# PinBoardJTAG20_10.net
KiCad netlist of a schematic drawn in Altium Designer
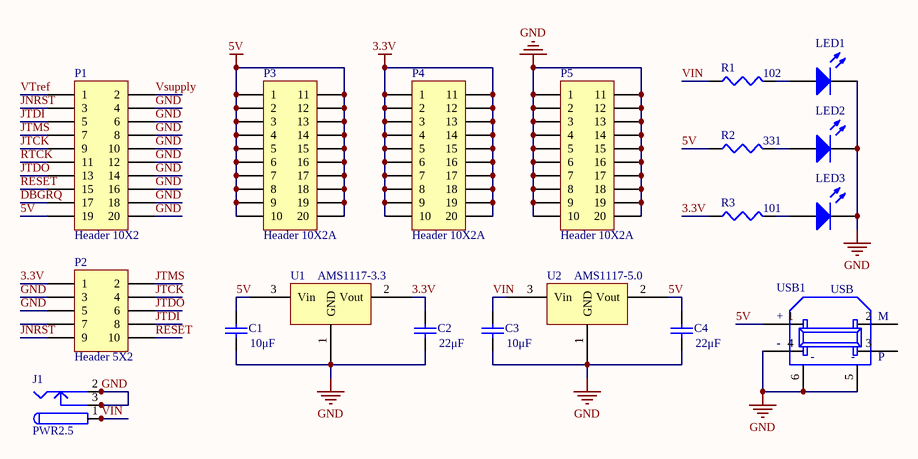
[diagram p0: PinBoardJTAG20_10.SchDoc]

(export (version "E")
  (design (tool "Eeschema 10.0.6"))
  (components
    (comp (ref "C1")
      (value "10μF")
      (footprint "1608[0603]")
      (description "Capacitor (Semiconductor SIM Model)")
      (fields (field (name "Comment") "Cap Semi") (field (name "PUBLISHER") "Altium Limited"))
      (libsource (lib "Miscellaneous Devices") (part "Cap Semi"))
    )
    (comp (ref "C2")
      (value "22μF")
      (footprint "1608[0603]")
      (description "Capacitor (Semiconductor SIM Model)")
      (fields (field (name "Comment") "Cap Semi") (field (name "PUBLISHER") "Altium Limited"))
      (libsource (lib "Miscellaneous Devices") (part "Cap Semi"))
    )
    (comp (ref "C3")
      (value "10μF")
      (footprint "1608[0603]")
      (description "Capacitor (Semiconductor SIM Model)")
      (fields (field (name "Comment") "Cap Semi") (field (name "PUBLISHER") "Altium Limited"))
      (libsource (lib "Miscellaneous Devices") (part "Cap Semi"))
    )
    (comp (ref "C4")
      (value "22μF")
      (footprint "1608[0603]")
      (description "Capacitor (Semiconductor SIM Model)")
      (fields (field (name "Comment") "Cap Semi") (field (name "PUBLISHER") "Altium Limited"))
      (libsource (lib "Miscellaneous Devices") (part "Cap Semi"))
    )
    (comp (ref "J1")
      (value "PWR2.5")
      (footprint "KLD-0202")
      (description "Low Voltage Power Supply Connector")
      (fields (field (name "PUBLISHER") "Altium Limited"))
      (libsource (lib "Miscellaneous Connectors") (part "PWR2.5"))
    )
    (comp (ref "LED1")
      (value "LED1")
      (footprint "BAT-2")
      (description "Typical RED GaAs LED")
      (fields (field (name "PUBLISHER") "Altium Limited"))
      (libsource (lib "Miscellaneous Devices") (part "LED1"))
    )
    (comp (ref "LED2")
      (value "LED1")
      (footprint "BAT-2")
      (description "Typical RED GaAs LED")
      (fields (field (name "PUBLISHER") "Altium Limited"))
      (libsource (lib "Miscellaneous Devices") (part "LED1"))
    )
    (comp (ref "LED3")
      (value "LED1")
      (footprint "BAT-2")
      (description "Typical RED GaAs LED")
      (fields (field (name "PUBLISHER") "Altium Limited"))
      (libsource (lib "Miscellaneous Devices") (part "LED1"))
    )
    (comp (ref "P1")
      (value "Header 10X2")
      (footprint "HDR2X10")
      (description "Header, 10-Pin, Dual row")
      (fields (field (name "PUBLISHER") "Altium Limited"))
      (libsource (lib "Miscellaneous Connectors") (part "Header 10X2"))
    )
    (comp (ref "P2")
      (value "Header 5X2")
      (footprint "HDR2X5")
      (description "Header, 5-Pin, Dual row")
      (fields (field (name "PUBLISHER") "Altium Limited"))
      (libsource (lib "Miscellaneous Connectors") (part "Header 5X2"))
    )
    (comp (ref "P3")
      (value "Header 10X2A")
      (footprint "HDR2X10_CEN")
      (description "Header, 10-Pin, Dual row")
      (fields (field (name "PUBLISHER") "Altium Limited"))
      (libsource (lib "Miscellaneous Connectors") (part "Header 10X2A"))
    )
    (comp (ref "P4")
      (value "Header 10X2A")
      (footprint "HDR2X10_CEN")
      (description "Header, 10-Pin, Dual row")
      (fields (field (name "PUBLISHER") "Altium Limited"))
      (libsource (lib "Miscellaneous Connectors") (part "Header 10X2A"))
    )
    (comp (ref "P5")
      (value "Header 10X2A")
      (footprint "HDR2X10_CEN")
      (description "Header, 10-Pin, Dual row")
      (fields (field (name "PUBLISHER") "Altium Limited"))
      (libsource (lib "Miscellaneous Connectors") (part "Header 10X2A"))
    )
    (comp (ref "R1")
      (value "102")
      (footprint "6-0805_N")
      (description "Resistor")
      (fields (field (name "Comment") "Res3") (field (name "PUBLISHER") "Altium Limited"))
      (libsource (lib "Miscellaneous Devices") (part "Res3"))
    )
    (comp (ref "R2")
      (value "331")
      (footprint "6-0805_N")
      (description "Resistor")
      (fields (field (name "Comment") "Res3") (field (name "PUBLISHER") "Altium Limited"))
      (libsource (lib "Miscellaneous Devices") (part "Res3"))
    )
    (comp (ref "R3")
      (value "101")
      (footprint "6-0805_N")
      (description "Resistor")
      (fields (field (name "Comment") "Res3") (field (name "PUBLISHER") "Altium Limited"))
      (libsource (lib "Miscellaneous Devices") (part "Res3"))
    )
    (comp (ref "U1")
      (value "AMS1117-3.3")
      (footprint "AMS1117-SOT223")
      (libsource (lib "Common") (part "AMS1117-3.3"))
    )
    (comp (ref "U2")
      (value "AMS1117-5.0")
      (footprint "AMS1117-SOT223")
      (libsource (lib "Common") (part "AMS1117-5.0"))
    )
    (comp (ref "USB1") (value "USB") (footprint "MICROUSB_D2S6") (libsource (lib "Common") (part "USB")))
  )
  (nets
    (net (code "1") (name "/DBGRQ") (class "Default")
      (node (ref "P1") (pin "17") (pinfunction "17_17") (pintype "passive"))
    )
    (net (code "2") (name "/JNRST") (class "Default")
      (node (ref "P1") (pin "3") (pinfunction "3_3") (pintype "passive"))
      (node (ref "P2") (pin "9") (pinfunction "9_9") (pintype "passive"))
    )
    (net (code "3") (name "/JTCK") (class "Default")
      (node (ref "P1") (pin "9") (pinfunction "9_9") (pintype "passive"))
      (node (ref "P2") (pin "4") (pinfunction "4_4") (pintype "passive"))
    )
    (net (code "4") (name "/JTDI") (class "Default")
      (node (ref "P1") (pin "5") (pinfunction "5_5") (pintype "passive"))
      (node (ref "P2") (pin "8") (pinfunction "8_8") (pintype "passive"))
    )
    (net (code "5") (name "/JTDO") (class "Default")
      (node (ref "P1") (pin "13") (pinfunction "13_13") (pintype "passive"))
      (node (ref "P2") (pin "6") (pinfunction "6_6") (pintype "passive"))
    )
    (net (code "6") (name "/JTMS") (class "Default")
      (node (ref "P1") (pin "7") (pinfunction "7_7") (pintype "passive"))
      (node (ref "P2") (pin "2") (pinfunction "2_2") (pintype "passive"))
    )
    (net (code "7") (name "/RESET") (class "Default")
      (node (ref "P1") (pin "15") (pinfunction "15_15") (pintype "passive"))
      (node (ref "P2") (pin "10") (pinfunction "10_10") (pintype "passive"))
    )
    (net (code "8") (name "/RTCK") (class "Default")
      (node (ref "P1") (pin "11") (pinfunction "11_11") (pintype "passive"))
    )
    (net (code "9") (name "/VIN") (class "Default")
      (node (ref "C3") (pin "2") (pinfunction "2_2") (pintype "passive"))
      (node (ref "J1") (pin "1") (pinfunction "1_1") (pintype "power_in"))
      (node (ref "J1") (pin "1A") (pinfunction "1A_1A") (pintype "power_in"))
      (node (ref "J1") (pin "1B") (pinfunction "1B_1B") (pintype "power_in"))
      (node (ref "R1") (pin "1") (pinfunction "1_1") (pintype "passive"))
      (node (ref "U2") (pin "3") (pinfunction "Vin_3") (pintype "passive"))
    )
    (net (code "10") (name "/VTref") (class "Default")
      (node (ref "P1") (pin "1") (pinfunction "1_1") (pintype "passive"))
    )
    (net (code "11") (name "/Vsupply") (class "Default")
      (node (ref "P1") (pin "2") (pinfunction "2_2") (pintype "passive"))
    )
    (net (code "12") (name "3.3V") (class "Default")
      (node (ref "C2") (pin "2") (pinfunction "2_2") (pintype "passive"))
      (node (ref "P2") (pin "1") (pinfunction "1_1") (pintype "passive"))
      (node (ref "P4") (pin "1") (pinfunction "1_1") (pintype "passive"))
      (node (ref "P4") (pin "10") (pinfunction "10_10") (pintype "passive"))
      (node (ref "P4") (pin "11") (pinfunction "11_11") (pintype "passive"))
      (node (ref "P4") (pin "12") (pinfunction "12_12") (pintype "passive"))
      (node (ref "P4") (pin "13") (pinfunction "13_13") (pintype "passive"))
      (node (ref "P4") (pin "14") (pinfunction "14_14") (pintype "passive"))
      (node (ref "P4") (pin "15") (pinfunction "15_15") (pintype "passive"))
      (node (ref "P4") (pin "16") (pinfunction "16_16") (pintype "passive"))
      (node (ref "P4") (pin "17") (pinfunction "17_17") (pintype "passive"))
      (node (ref "P4") (pin "18") (pinfunction "18_18") (pintype "passive"))
      (node (ref "P4") (pin "19") (pinfunction "19_19") (pintype "passive"))
      (node (ref "P4") (pin "2") (pinfunction "2_2") (pintype "passive"))
      (node (ref "P4") (pin "20") (pinfunction "20_20") (pintype "passive"))
      (node (ref "P4") (pin "3") (pinfunction "3_3") (pintype "passive"))
      (node (ref "P4") (pin "4") (pinfunction "4_4") (pintype "passive"))
      (node (ref "P4") (pin "5") (pinfunction "5_5") (pintype "passive"))
      (node (ref "P4") (pin "6") (pinfunction "6_6") (pintype "passive"))
      (node (ref "P4") (pin "7") (pinfunction "7_7") (pintype "passive"))
      (node (ref "P4") (pin "8") (pinfunction "8_8") (pintype "passive"))
      (node (ref "P4") (pin "9") (pinfunction "9_9") (pintype "passive"))
      (node (ref "R3") (pin "1") (pinfunction "1_1") (pintype "passive"))
      (node (ref "U1") (pin "2") (pinfunction "Vout_2") (pintype "passive"))
    )
    (net (code "13") (name "5V") (class "Default")
      (node (ref "C1") (pin "2") (pinfunction "2_2") (pintype "passive"))
      (node (ref "C4") (pin "2") (pinfunction "2_2") (pintype "passive"))
      (node (ref "P1") (pin "19") (pinfunction "19_19") (pintype "passive"))
      (node (ref "P3") (pin "1") (pinfunction "1_1") (pintype "passive"))
      (node (ref "P3") (pin "10") (pinfunction "10_10") (pintype "passive"))
      (node (ref "P3") (pin "11") (pinfunction "11_11") (pintype "passive"))
      (node (ref "P3") (pin "12") (pinfunction "12_12") (pintype "passive"))
      (node (ref "P3") (pin "13") (pinfunction "13_13") (pintype "passive"))
      (node (ref "P3") (pin "14") (pinfunction "14_14") (pintype "passive"))
      (node (ref "P3") (pin "15") (pinfunction "15_15") (pintype "passive"))
      (node (ref "P3") (pin "16") (pinfunction "16_16") (pintype "passive"))
      (node (ref "P3") (pin "17") (pinfunction "17_17") (pintype "passive"))
      (node (ref "P3") (pin "18") (pinfunction "18_18") (pintype "passive"))
      (node (ref "P3") (pin "19") (pinfunction "19_19") (pintype "passive"))
      (node (ref "P3") (pin "2") (pinfunction "2_2") (pintype "passive"))
      (node (ref "P3") (pin "20") (pinfunction "20_20") (pintype "passive"))
      (node (ref "P3") (pin "3") (pinfunction "3_3") (pintype "passive"))
      (node (ref "P3") (pin "4") (pinfunction "4_4") (pintype "passive"))
      (node (ref "P3") (pin "5") (pinfunction "5_5") (pintype "passive"))
      (node (ref "P3") (pin "6") (pinfunction "6_6") (pintype "passive"))
      (node (ref "P3") (pin "7") (pinfunction "7_7") (pintype "passive"))
      (node (ref "P3") (pin "8") (pinfunction "8_8") (pintype "passive"))
      (node (ref "P3") (pin "9") (pinfunction "9_9") (pintype "passive"))
      (node (ref "R2") (pin "1") (pinfunction "1_1") (pintype "passive"))
      (node (ref "U1") (pin "3") (pinfunction "Vin_3") (pintype "passive"))
      (node (ref "U2") (pin "2") (pinfunction "Vout_2") (pintype "passive"))
      (node (ref "USB1") (pin "1") (pinfunction "VB_1") (pintype "passive"))
    )
    (net (code "14") (name "GND") (class "Default")
      (node (ref "C1") (pin "1") (pinfunction "1_1") (pintype "passive"))
      (node (ref "C2") (pin "1") (pinfunction "1_1") (pintype "passive"))
      (node (ref "C3") (pin "1") (pinfunction "1_1") (pintype "passive"))
      (node (ref "C4") (pin "1") (pinfunction "1_1") (pintype "passive"))
      (node (ref "J1") (pin "2") (pinfunction "2_2") (pintype "power_in"))
      (node (ref "J1") (pin "2A") (pinfunction "2A_2A") (pintype "power_in"))
      (node (ref "J1") (pin "2B") (pinfunction "2B_2B") (pintype "power_in"))
      (node (ref "J1") (pin "3") (pinfunction "3_3") (pintype "power_in"))
      (node (ref "J1") (pin "3A") (pinfunction "3A_3A") (pintype "power_in"))
      (node (ref "J1") (pin "3B") (pinfunction "3B_3B") (pintype "power_in"))
      (node (ref "LED1") (pin "2") (pinfunction "K_2") (pintype "passive"))
      (node (ref "LED2") (pin "2") (pinfunction "K_2") (pintype "passive"))
      (node (ref "LED3") (pin "2") (pinfunction "K_2") (pintype "passive"))
      (node (ref "P1") (pin "10") (pinfunction "10_10") (pintype "passive"))
      (node (ref "P1") (pin "12") (pinfunction "12_12") (pintype "passive"))
      (node (ref "P1") (pin "14") (pinfunction "14_14") (pintype "passive"))
      (node (ref "P1") (pin "16") (pinfunction "16_16") (pintype "passive"))
      (node (ref "P1") (pin "18") (pinfunction "18_18") (pintype "passive"))
      (node (ref "P1") (pin "20") (pinfunction "20_20") (pintype "passive"))
      (node (ref "P1") (pin "4") (pinfunction "4_4") (pintype "passive"))
      (node (ref "P1") (pin "6") (pinfunction "6_6") (pintype "passive"))
      (node (ref "P1") (pin "8") (pinfunction "8_8") (pintype "passive"))
      (node (ref "P2") (pin "3") (pinfunction "3_3") (pintype "passive"))
      (node (ref "P2") (pin "5") (pinfunction "5_5") (pintype "passive"))
      (node (ref "P5") (pin "1") (pinfunction "1_1") (pintype "passive"))
      (node (ref "P5") (pin "10") (pinfunction "10_10") (pintype "passive"))
      (node (ref "P5") (pin "11") (pinfunction "11_11") (pintype "passive"))
      (node (ref "P5") (pin "12") (pinfunction "12_12") (pintype "passive"))
      (node (ref "P5") (pin "13") (pinfunction "13_13") (pintype "passive"))
      (node (ref "P5") (pin "14") (pinfunction "14_14") (pintype "passive"))
      (node (ref "P5") (pin "15") (pinfunction "15_15") (pintype "passive"))
      (node (ref "P5") (pin "16") (pinfunction "16_16") (pintype "passive"))
      (node (ref "P5") (pin "17") (pinfunction "17_17") (pintype "passive"))
      (node (ref "P5") (pin "18") (pinfunction "18_18") (pintype "passive"))
      (node (ref "P5") (pin "19") (pinfunction "19_19") (pintype "passive"))
      (node (ref "P5") (pin "2") (pinfunction "2_2") (pintype "passive"))
      (node (ref "P5") (pin "20") (pinfunction "20_20") (pintype "passive"))
      (node (ref "P5") (pin "3") (pinfunction "3_3") (pintype "passive"))
      (node (ref "P5") (pin "4") (pinfunction "4_4") (pintype "passive"))
      (node (ref "P5") (pin "5") (pinfunction "5_5") (pintype "passive"))
      (node (ref "P5") (pin "6") (pinfunction "6_6") (pintype "passive"))
      (node (ref "P5") (pin "7") (pinfunction "7_7") (pintype "passive"))
      (node (ref "P5") (pin "8") (pinfunction "8_8") (pintype "passive"))
      (node (ref "P5") (pin "9") (pinfunction "9_9") (pintype "passive"))
      (node (ref "U1") (pin "1") (pinfunction "GND_1") (pintype "passive"))
      (node (ref "U2") (pin "1") (pinfunction "GND_1") (pintype "passive"))
      (node (ref "USB1") (pin "4") (pinfunction "G_4") (pintype "passive"))
      (node (ref "USB1") (pin "5") (pinfunction "G_5") (pintype "passive"))
      (node (ref "USB1") (pin "6") (pinfunction "G_6") (pintype "passive"))
    )
    (net (code "15") (name "Net-(LED1-A)") (class "Default")
      (node (ref "LED1") (pin "1") (pinfunction "A_1") (pintype "passive"))
      (node (ref "R1") (pin "2") (pinfunction "2_2") (pintype "passive"))
    )
    (net (code "16") (name "Net-(LED2-A)") (class "Default")
      (node (ref "LED2") (pin "1") (pinfunction "A_1") (pintype "passive"))
      (node (ref "R2") (pin "2") (pinfunction "2_2") (pintype "passive"))
    )
    (net (code "17") (name "Net-(LED3-A)") (class "Default")
      (node (ref "LED3") (pin "1") (pinfunction "A_1") (pintype "passive"))
      (node (ref "R3") (pin "2") (pinfunction "2_2") (pintype "passive"))
    )
    (net (code "18") (name "unconnected-(P2-Pad7)") (class "Default")
      (node (ref "P2") (pin "7") (pinfunction "7_7") (pintype "passive"))
    )
    (net (code "19") (name "unconnected-(USB1-DM-Pad2)") (class "Default")
      (node (ref "USB1") (pin "2") (pinfunction "DM_2") (pintype "passive"))
    )
    (net (code "20") (name "unconnected-(USB1-DP-Pad3)") (class "Default")
      (node (ref "USB1") (pin "3") (pinfunction "DP_3") (pintype "passive"))
    )
  )
)
